# Convertisseur_SPI_UART.net
KiCad netlist of a schematic drawn in Altium Designer
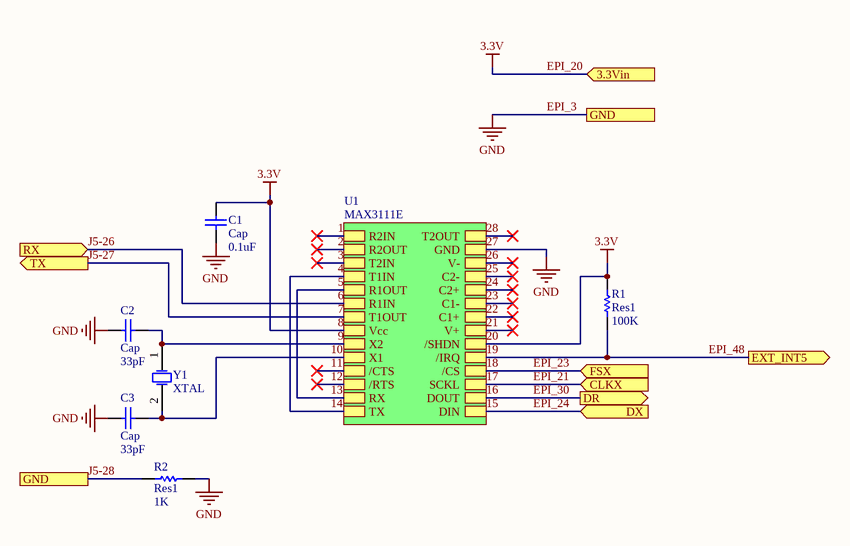
[diagram p0: Convertisseur_SPI_UART.SchDoc]

(export (version "E")
  (design (tool "Eeschema 10.0.6"))
  (components
    (comp (ref "C1")
      (value "Cap")
      (footprint "RAD-0.3")
      (description "Capacitor")
      (fields (field (name "ALTIUM_VALUE") "0.1uF") (field (name "PUBLISHER") "Altium Limited"))
      (libsource (lib "Miscellaneous Devices") (part "Cap"))
    )
    (comp (ref "C2")
      (value "Cap")
      (footprint "RAD-0.3")
      (description "Capacitor")
      (fields (field (name "ALTIUM_VALUE") "33pF") (field (name "PUBLISHER") "Altium Limited"))
      (libsource (lib "Miscellaneous Devices") (part "Cap"))
    )
    (comp (ref "C3")
      (value "Cap")
      (footprint "RAD-0.3")
      (description "Capacitor")
      (fields (field (name "ALTIUM_VALUE") "33pF") (field (name "PUBLISHER") "Altium Limited"))
      (libsource (lib "Miscellaneous Devices") (part "Cap"))
    )
    (comp (ref "R1")
      (value "Res1")
      (footprint "AXIAL-0.3")
      (description "Resistor")
      (fields (field (name "ALTIUM_VALUE") "100K") (field (name "PUBLISHER") "Altium Limited"))
      (libsource (lib "Miscellaneous Devices") (part "Res1"))
    )
    (comp (ref "R2")
      (value "Res1")
      (footprint "AXIAL-0.3")
      (description "Resistor")
      (fields (field (name "ALTIUM_VALUE") "1K") (field (name "PUBLISHER") "Altium Limited"))
      (libsource (lib "Miscellaneous Devices") (part "Res1"))
    )
    (comp (ref "Y1")
      (value "XTAL")
      (footprint "R38")
      (description "Crystal Oscillator")
      (fields (field (name "PUBLISHER") "Altium Limited"))
      (libsource (lib "Miscellaneous Devices") (part "XTAL"))
    )
  )
  (nets
    (net (code "6") (name "/9") (class "Default")
      (node (ref "C2") (pin "2") (pinfunction "2_2") (pintype "passive"))
      (node (ref "Y1") (pin "1") (pinfunction "OSC1_1") (pintype "passive"))
    )
    (net (code "7") (name "/10") (class "Default")
      (node (ref "C3") (pin "2") (pinfunction "2_2") (pintype "passive"))
      (node (ref "Y1") (pin "2") (pinfunction "OSC2_2") (pintype "passive"))
    )
    (net (code "16") (name "/19") (class "Default")
      (node (ref "R1") (pin "2") (pinfunction "2_2") (pintype "passive"))
    )
    (net (code "24") (name "3.3V") (class "Default")
      (node (ref "C1") (pin "2") (pinfunction "2_2") (pintype "passive"))
      (node (ref "R1") (pin "1") (pinfunction "1_1") (pintype "passive"))
    )
    (net (code "25") (name "GND") (class "Default")
      (node (ref "C1") (pin "1") (pinfunction "1_1") (pintype "passive"))
      (node (ref "C2") (pin "1") (pinfunction "1_1") (pintype "passive"))
      (node (ref "C3") (pin "1") (pinfunction "1_1") (pintype "passive"))
      (node (ref "R2") (pin "1") (pinfunction "1_1") (pintype "passive"))
      (node (ref "R2") (pin "2") (pinfunction "2_2") (pintype "passive"))
    )
  )
)
